# Adafruit_MAX31850.net
KiCad netlist of a schematic drawn in EAGLE
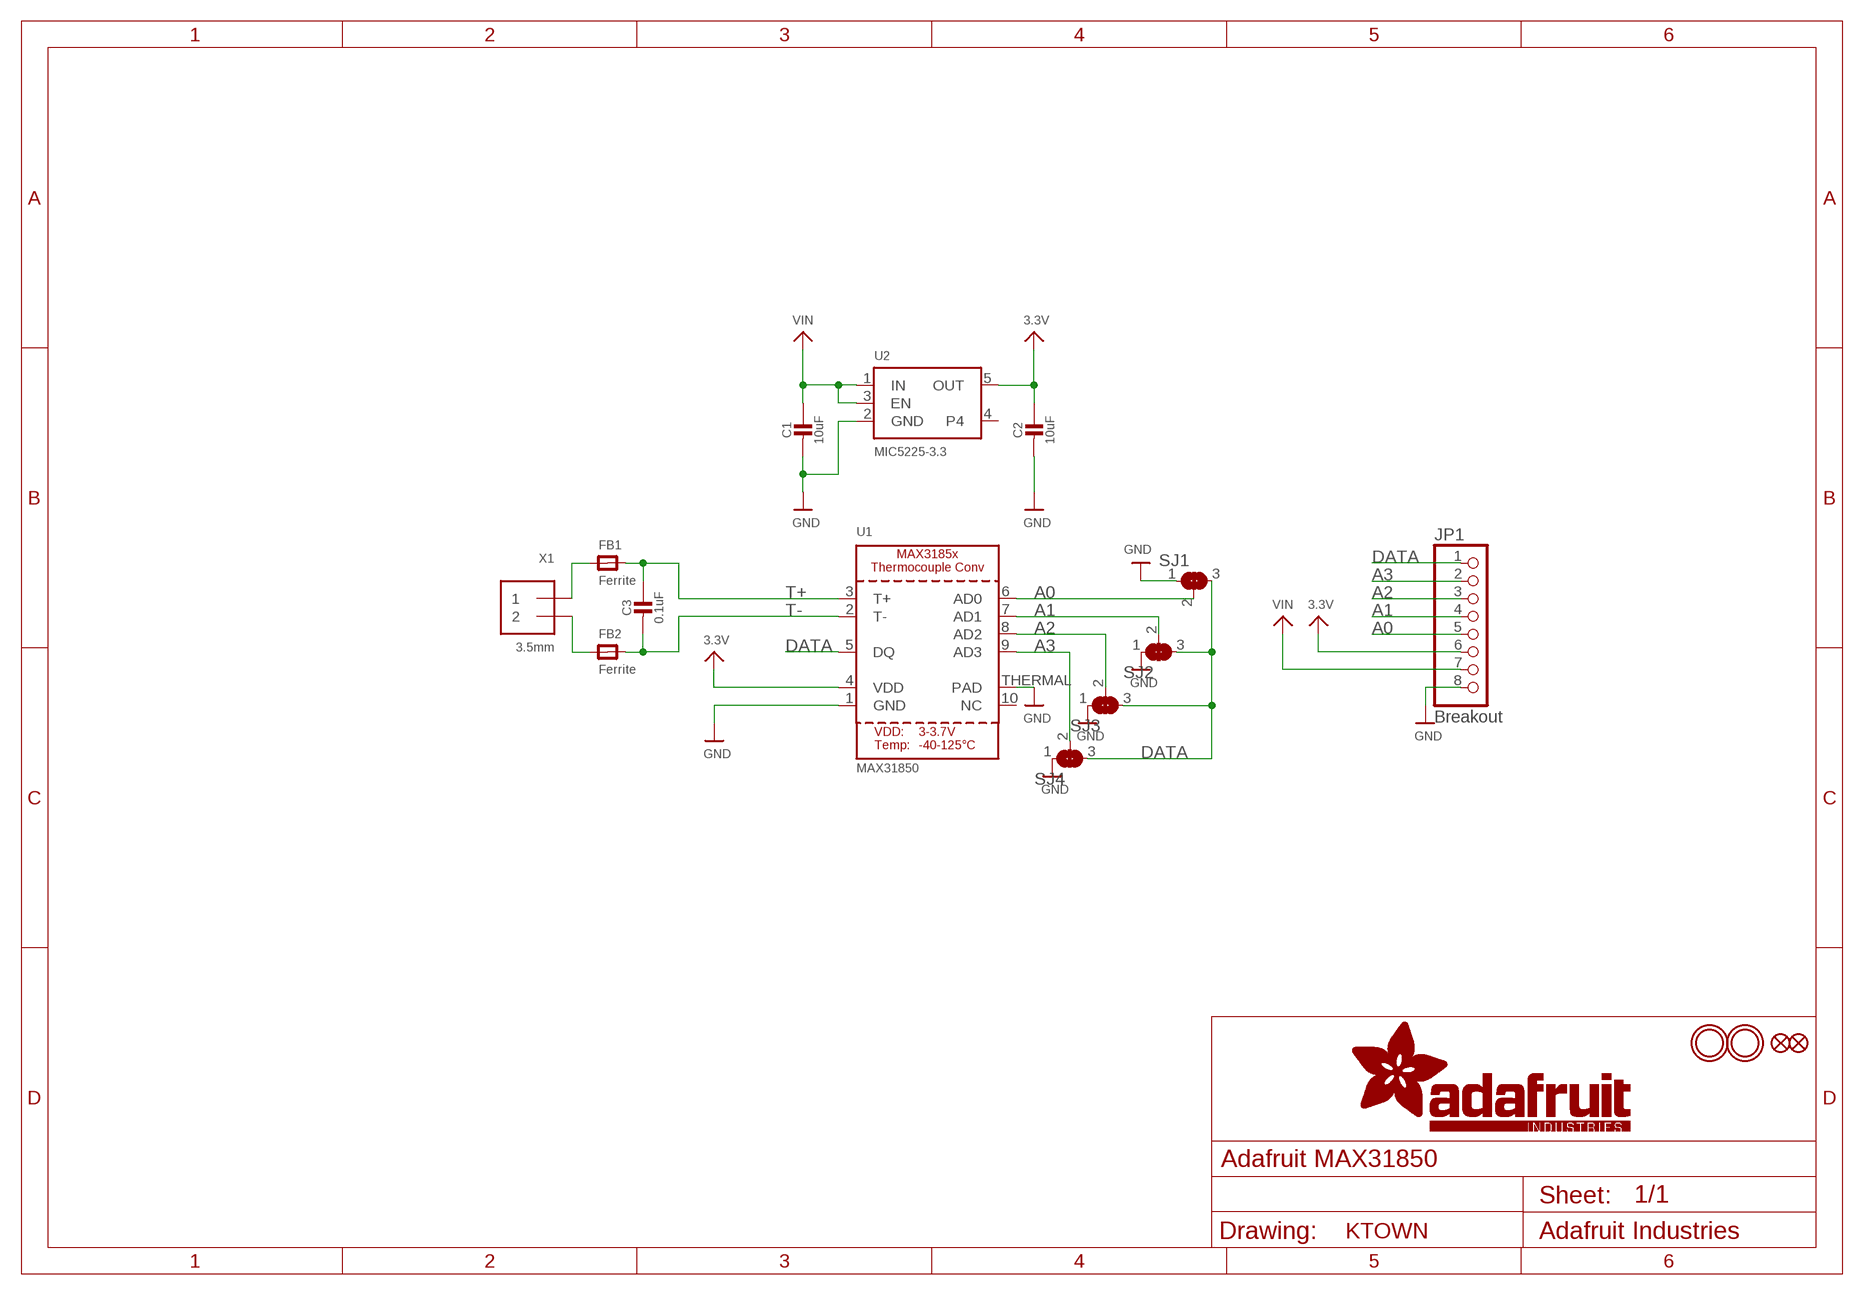
[diagram p0: schematic, sheet 1]

(export (version "E")
  (design (tool "Eeschema 10.0.6"))
  (components
    (comp (ref "C1")
      (value "10uF")
      (footprint "eagle-import:0805-NO")
      (libsource (lib "eagle-import") (part "CAP_CERAMIC0805-NOOUTLINE"))
    )
    (comp (ref "C2")
      (value "10uF")
      (footprint "eagle-import:0805-NO")
      (libsource (lib "eagle-import") (part "CAP_CERAMIC0805-NOOUTLINE"))
    )
    (comp (ref "C3")
      (value "0.1uF")
      (footprint "eagle-import:0805-NO")
      (libsource (lib "eagle-import") (part "CAP_CERAMIC0805-NOOUTLINE"))
    )
    (comp (ref "FB1")
      (value "Ferrite")
      (footprint "eagle-import:0805")
      (libsource (lib "eagle-import") (part "FERRITE0805"))
    )
    (comp (ref "FB2")
      (value "Ferrite")
      (footprint "eagle-import:0805")
      (libsource (lib "eagle-import") (part "FERRITE0805"))
    )
    (comp (ref "FID1")
      (value "FIDUCIAL\"\"")
      (footprint "eagle-import:FIDUCIAL_1MM")
      (libsource (lib "eagle-import") (part "FIDUCIAL{dblquote}{dblquote}"))
    )
    (comp (ref "FID2")
      (value "FIDUCIAL\"\"")
      (footprint "eagle-import:FIDUCIAL_1MM")
      (libsource (lib "eagle-import") (part "FIDUCIAL{dblquote}{dblquote}"))
    )
    (comp (ref "JP1")
      (value "Breakout")
      (footprint "eagle-import:1X08_ROUND_70")
      (libsource (lib "eagle-import") (part "HEADER-1X870MIL"))
    )
    (comp (ref "SJ1")
      (value "SOLDERJUMPER_2WAY")
      (footprint "eagle-import:SOLDERJUMPER_2WAY_OPEN_NOPASTE")
      (libsource (lib "eagle-import") (part "SOLDERJUMPER_2WAY"))
    )
    (comp (ref "SJ2")
      (value "SOLDERJUMPER_2WAY")
      (footprint "eagle-import:SOLDERJUMPER_2WAY_OPEN_NOPASTE")
      (libsource (lib "eagle-import") (part "SOLDERJUMPER_2WAY"))
    )
    (comp (ref "SJ3")
      (value "SOLDERJUMPER_2WAY")
      (footprint "eagle-import:SOLDERJUMPER_2WAY_OPEN_NOPASTE")
      (libsource (lib "eagle-import") (part "SOLDERJUMPER_2WAY"))
    )
    (comp (ref "SJ4")
      (value "SOLDERJUMPER_2WAY")
      (footprint "eagle-import:SOLDERJUMPER_2WAY_OPEN_NOPASTE")
      (libsource (lib "eagle-import") (part "SOLDERJUMPER_2WAY"))
    )
    (comp (ref "U$8")
      (value "MOUNTINGHOLE2.5")
      (footprint "eagle-import:MOUNTINGHOLE_2.5_PLATED")
      (libsource (lib "eagle-import") (part "MOUNTINGHOLE2.5"))
    )
    (comp (ref "U$9")
      (value "MOUNTINGHOLE2.5")
      (footprint "eagle-import:MOUNTINGHOLE_2.5_PLATED")
      (libsource (lib "eagle-import") (part "MOUNTINGHOLE2.5"))
    )
    (comp (ref "U1")
      (value "MAX31850")
      (footprint "eagle-import:TDFN10_3X4MM")
      (libsource (lib "eagle-import") (part "MAX3185X"))
    )
    (comp (ref "U2")
      (value "MIC5225-3.3")
      (footprint "eagle-import:SOT23-5")
      (libsource (lib "eagle-import") (part "VREG_SOT23-5"))
    )
    (comp (ref "X1")
      (value "3.5mm")
      (footprint "eagle-import:TERMBLOCK_1X2-3.5MM")
      (libsource (lib "eagle-import") (part "TERMBLOCK_1X2"))
    )
  )
  (nets
    (net (code "1") (name "/A0") (class "Default")
      (node (ref "JP1") (pin "5") (pinfunction "5_5") (pintype "passive"))
      (node (ref "SJ1") (pin "2") (pinfunction "2_2") (pintype "passive"))
      (node (ref "U1") (pin "6") (pinfunction "AD0_6") (pintype "input"))
    )
    (net (code "2") (name "/A1") (class "Default")
      (node (ref "JP1") (pin "4") (pinfunction "4_4") (pintype "passive"))
      (node (ref "SJ2") (pin "2") (pinfunction "2_2") (pintype "passive"))
      (node (ref "U1") (pin "7") (pinfunction "AD1_7") (pintype "input"))
    )
    (net (code "3") (name "/A2") (class "Default")
      (node (ref "JP1") (pin "3") (pinfunction "3_3") (pintype "passive"))
      (node (ref "SJ3") (pin "2") (pinfunction "2_2") (pintype "passive"))
      (node (ref "U1") (pin "8") (pinfunction "AD2_8") (pintype "input"))
    )
    (net (code "4") (name "/A3") (class "Default")
      (node (ref "JP1") (pin "2") (pinfunction "2_2") (pintype "passive"))
      (node (ref "SJ4") (pin "2") (pinfunction "2_2") (pintype "passive"))
      (node (ref "U1") (pin "9") (pinfunction "AD3_9") (pintype "input"))
    )
    (net (code "5") (name "/DATA") (class "Default")
      (node (ref "JP1") (pin "1") (pinfunction "1_1") (pintype "passive"))
      (node (ref "SJ1") (pin "3") (pinfunction "3_3") (pintype "passive"))
      (node (ref "SJ2") (pin "3") (pinfunction "3_3") (pintype "passive"))
      (node (ref "SJ3") (pin "3") (pinfunction "3_3") (pintype "passive"))
      (node (ref "SJ4") (pin "3") (pinfunction "3_3") (pintype "passive"))
      (node (ref "U1") (pin "5") (pinfunction "DQ_5") (pintype "bidirectional"))
    )
    (net (code "6") (name "/T+") (class "Default")
      (node (ref "C3") (pin "1") (pinfunction "1_1") (pintype "passive"))
      (node (ref "FB1") (pin "2") (pinfunction "P$2_2") (pintype "passive"))
      (node (ref "U1") (pin "3") (pinfunction "T+_3") (pintype "input"))
    )
    (net (code "7") (name "/T-") (class "Default")
      (node (ref "C3") (pin "2") (pinfunction "2_2") (pintype "passive"))
      (node (ref "FB2") (pin "2") (pinfunction "P$2_2") (pintype "passive"))
      (node (ref "U1") (pin "2") (pinfunction "T-_2") (pintype "input"))
    )
    (net (code "8") (name "3.3V") (class "Default")
      (node (ref "C2") (pin "1") (pinfunction "1_1") (pintype "passive"))
      (node (ref "JP1") (pin "6") (pinfunction "6_6") (pintype "passive"))
      (node (ref "U1") (pin "4") (pinfunction "VDD_4") (pintype "power_in"))
      (node (ref "U2") (pin "5") (pinfunction "OUT_5") (pintype "power_in"))
    )
    (net (code "9") (name "GND") (class "Default")
      (node (ref "C1") (pin "2") (pinfunction "2_2") (pintype "passive"))
      (node (ref "C2") (pin "2") (pinfunction "2_2") (pintype "passive"))
      (node (ref "JP1") (pin "8") (pinfunction "8_8") (pintype "passive"))
      (node (ref "SJ1") (pin "1") (pinfunction "1_1") (pintype "passive"))
      (node (ref "SJ2") (pin "1") (pinfunction "1_1") (pintype "passive"))
      (node (ref "SJ3") (pin "1") (pinfunction "1_1") (pintype "passive"))
      (node (ref "SJ4") (pin "1") (pinfunction "1_1") (pintype "passive"))
      (node (ref "U1") (pin "1") (pinfunction "GND_1") (pintype "power_in"))
      (node (ref "U1") (pin "THERMAL") (pinfunction "PAD_THERMAL") (pintype "passive"))
      (node (ref "U2") (pin "2") (pinfunction "GND_2") (pintype "power_in"))
    )
    (net (code "10") (name "Net-(FB1-P$1)") (class "Default")
      (node (ref "FB1") (pin "1") (pinfunction "P$1_1") (pintype "passive"))
      (node (ref "X1") (pin "1") (pinfunction "1_1") (pintype "passive"))
    )
    (net (code "11") (name "Net-(FB2-P$1)") (class "Default")
      (node (ref "FB2") (pin "1") (pinfunction "P$1_1") (pintype "passive"))
      (node (ref "X1") (pin "2") (pinfunction "2_2") (pintype "passive"))
    )
    (net (code "12") (name "VIN") (class "Default")
      (node (ref "C1") (pin "1") (pinfunction "1_1") (pintype "passive"))
      (node (ref "JP1") (pin "7") (pinfunction "7_7") (pintype "passive"))
      (node (ref "U2") (pin "1") (pinfunction "IN_1") (pintype "power_in"))
      (node (ref "U2") (pin "3") (pinfunction "EN_3") (pintype "input"))
    )
    (net (code "13") (name "unconnected-(U1-NC-Pad10)") (class "Default")
      (node (ref "U1") (pin "10") (pinfunction "NC_10") (pintype "no_connect"))
    )
    (net (code "14") (name "unconnected-(U2-P4-Pad4)") (class "Default")
      (node (ref "U2") (pin "4") (pinfunction "P4_4") (pintype "bidirectional"))
    )
  )
)
